# soundfield_board_40720_15mm.net
KiCad netlist of a schematic drawn in EAGLE
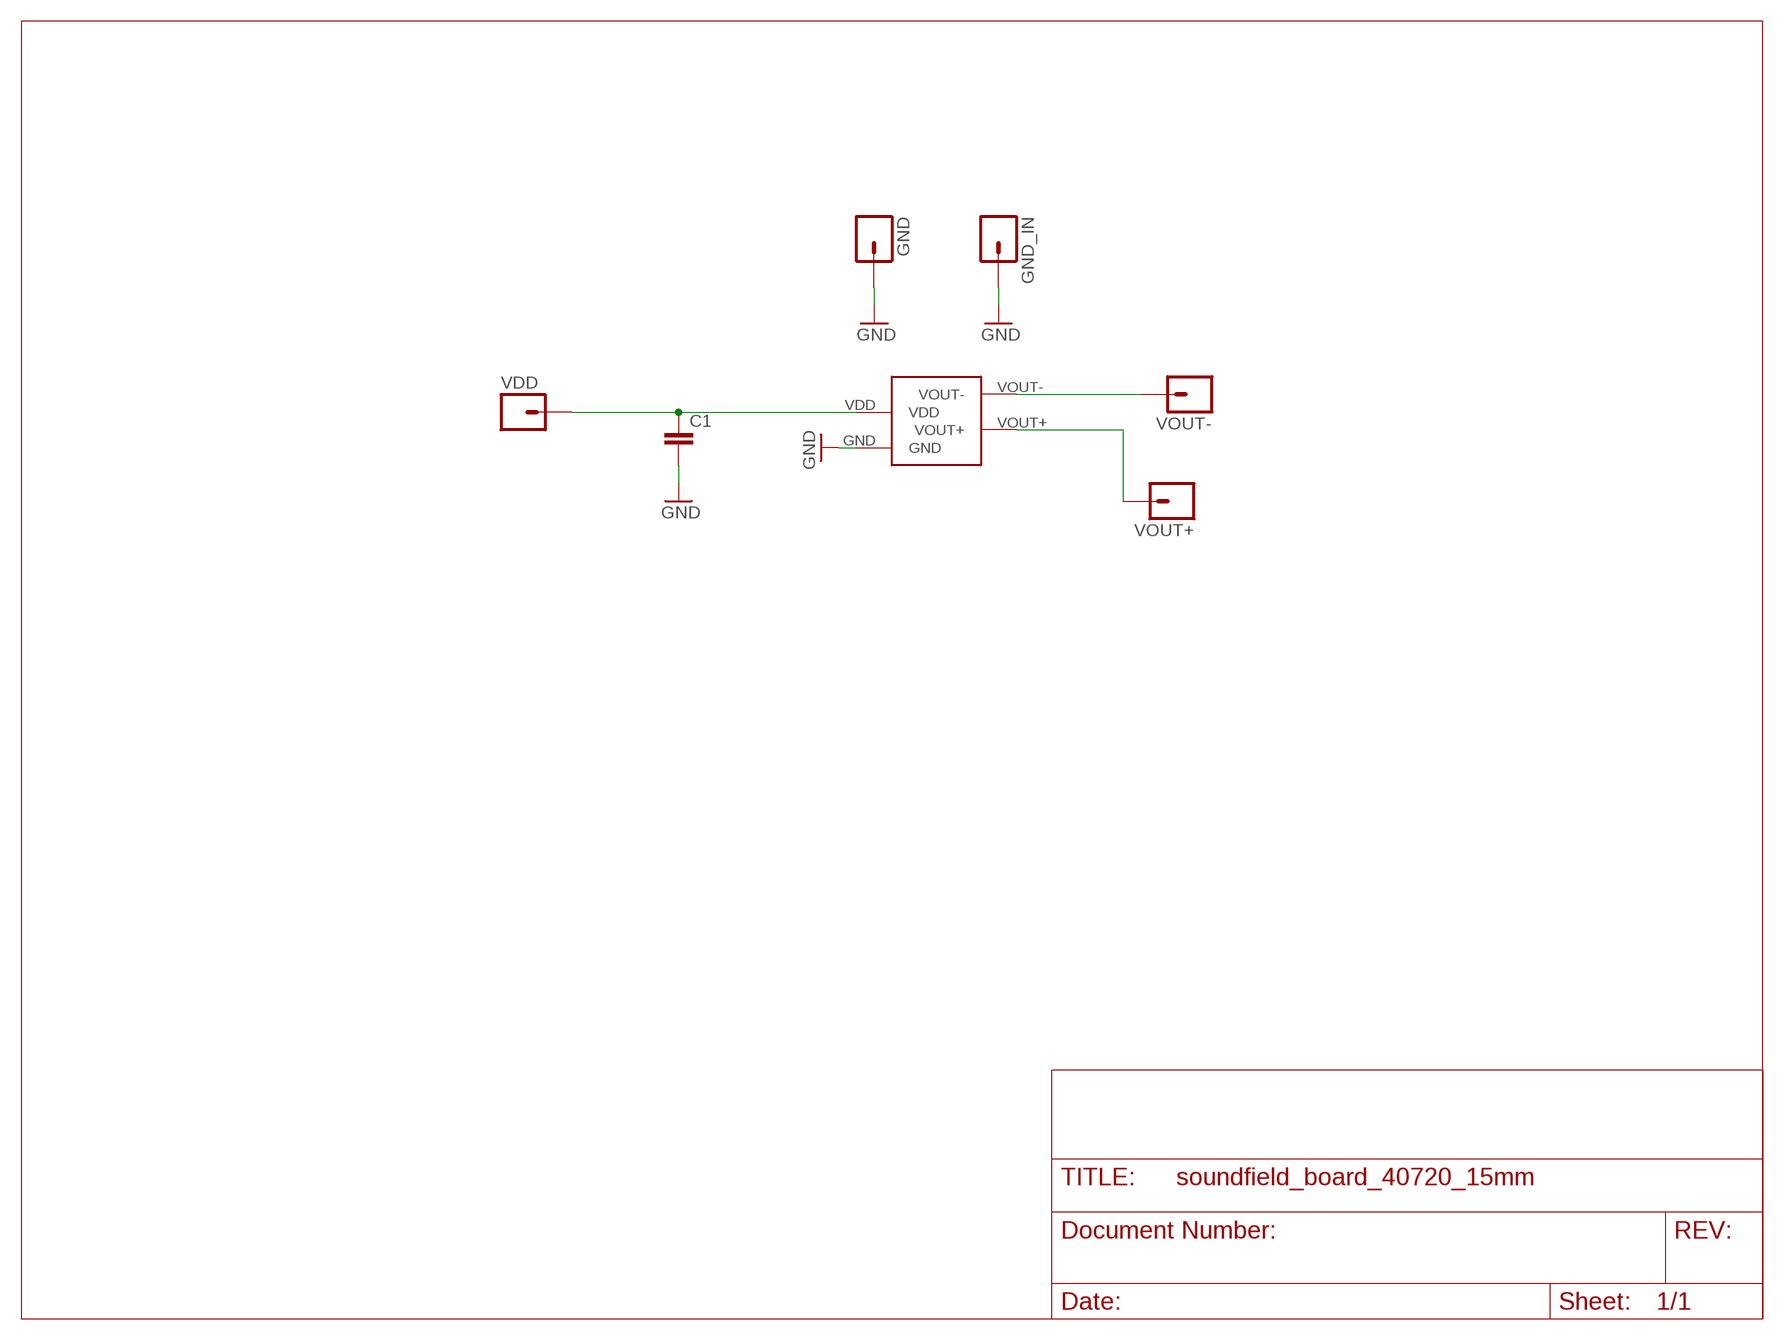
[diagram p0: schematic, sheet 1]

(export (version "E")
  (design (tool "Eeschema 10.0.6"))
  (components
    (comp (ref "C1")
      (value "0.1UF-16V(+-10%)(0402)")
      (footprint "eagle-import:0402-CAP")
      (libsource (lib "eagle-import") (part "0.1UF-16V(+-10%)(0402)"))
    )
    (comp (ref "GND")
      (value "M01PTH_NO_SILK_YES_STOP")
      (footprint "eagle-import:1X01_NO_SILK")
      (libsource (lib "eagle-import") (part "CM-SparkFun-Connectors-large_hole_M01PTH_NO_SILK_YES_STOP"))
    )
    (comp (ref "GND_IN")
      (value "M01PTH_NO_SILK_YES_STOP")
      (footprint "eagle-import:1X01_NO_SILK")
      (libsource (lib "eagle-import") (part "M01PTH_NO_SILK_YES_STOP"))
    )
    (comp (ref "U$1")
      (value "MEMS_ICS_40720")
      (footprint "eagle-import: MEMS_ICS_40720")
      (libsource (lib "eagle-import") (part " MEMS_ICS_40720"))
    )
    (comp (ref "VDD")
      (value "M01PTH_NO_SILK_YES_STOP")
      (footprint "eagle-import:1X01_NO_SILK")
      (libsource (lib "eagle-import") (part "M01PTH_NO_SILK_YES_STOP"))
    )
    (comp (ref "VOUT+")
      (value "M01PTH_NO_SILK_YES_STOP")
      (footprint "eagle-import:1X01_NO_SILK")
      (libsource (lib "eagle-import") (part "M01PTH_NO_SILK_YES_STOP"))
    )
    (comp (ref "VOUT-")
      (value "M01PTH_NO_SILK_YES_STOP")
      (footprint "eagle-import:1X01_NO_SILK")
      (libsource (lib "eagle-import") (part "M01PTH_NO_SILK_YES_STOP"))
    )
  )
  (nets
    (net (code "1") (name "GND") (class "Default")
      (node (ref "C1") (pin "2") (pinfunction "2_2") (pintype "passive"))
      (node (ref "GND") (pin "1") (pinfunction "1_1") (pintype "passive"))
      (node (ref "GND_IN") (pin "1") (pinfunction "1_1") (pintype "passive"))
      (node (ref "U$1") (pin "GND") (pinfunction "GND_GND") (pintype "input"))
    )
    (net (code "2") (name "Net-(C1-Pad1)") (class "Default")
      (node (ref "C1") (pin "1") (pinfunction "1_1") (pintype "passive"))
      (node (ref "U$1") (pin "VDD") (pinfunction "VDD_VDD") (pintype "power_in"))
      (node (ref "VDD") (pin "1") (pinfunction "1_1") (pintype "passive"))
    )
    (net (code "3") (name "Net-(U$1-PadVOUT+)") (class "Default")
      (node (ref "U$1") (pin "VOUT+") (pinfunction "VOUT+_VOUT+") (pintype "input"))
      (node (ref "VOUT+") (pin "1") (pinfunction "1_1") (pintype "passive"))
    )
    (net (code "4") (name "Net-(U$1-PadVOUT-)") (class "Default")
      (node (ref "U$1") (pin "VOUT-") (pinfunction "VOUT-_VOUT-") (pintype "input"))
      (node (ref "VOUT-") (pin "1") (pinfunction "1_1") (pintype "passive"))
    )
  )
)
